# generator_cd4047.net
KiCad netlist of a schematic drawn in EAGLE
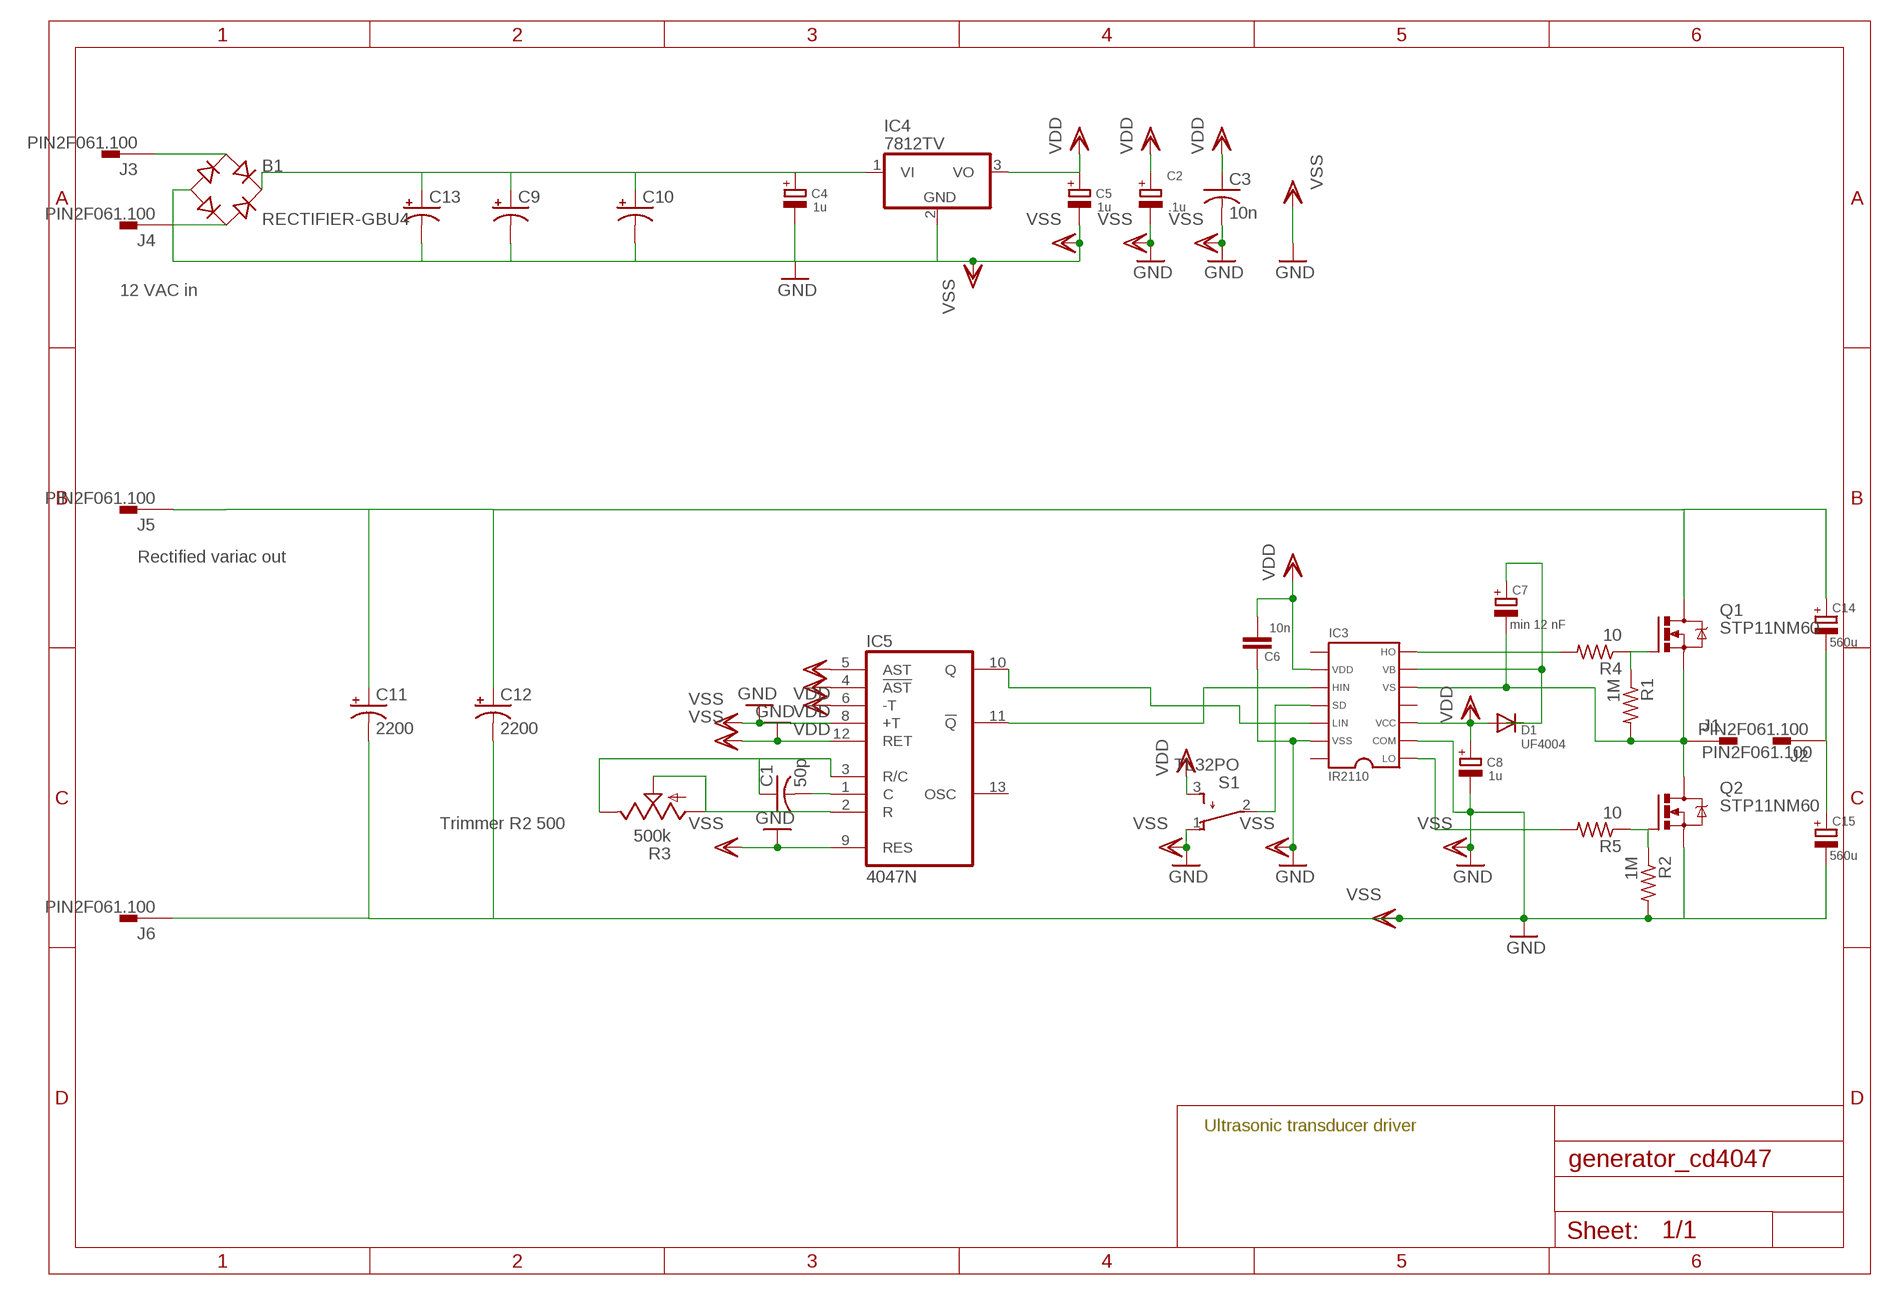
[diagram p0: schematic, sheet 1]

(export (version "E")
  (design (tool "Eeschema 10.0.6"))
  (components
    (comp (ref "B1")
      (value "RECTIFIER-GBU4")
      (footprint "eagle-import:GBU4")
      (libsource (lib "eagle-import") (part "RECTIFIER-GBU4"))
    )
    (comp (ref "C1")
      (value "50p")
      (footprint "eagle-import:C075-042X103")
      (libsource (lib "eagle-import") (part "C-US075-042X103"))
    )
    (comp (ref "C2")
      (value ".1u")
      (footprint "eagle-import:E5-8,5")
      (libsource (lib "eagle-import") (part "CPOL-EUE5-8.5"))
    )
    (comp (ref "C3")
      (value "10n")
      (footprint "eagle-import:C075-042X103")
      (libsource (lib "eagle-import") (part "C-US075-042X103"))
    )
    (comp (ref "C4")
      (value "1u")
      (footprint "eagle-import:E5-8,5")
      (libsource (lib "eagle-import") (part "CPOL-EUE5-8.5"))
    )
    (comp (ref "C5")
      (value "1u")
      (footprint "eagle-import:E5-8,5")
      (libsource (lib "eagle-import") (part "CPOL-EUE5-8.5"))
    )
    (comp (ref "C6")
      (value "10n")
      (footprint "eagle-import:C075-052X106")
      (libsource (lib "eagle-import") (part "C-EU075-052X106"))
    )
    (comp (ref "C7")
      (value "min 12 nF")
      (footprint "eagle-import:E5-8,5")
      (libsource (lib "eagle-import") (part "CPOL-EUE5-8.5"))
    )
    (comp (ref "C8")
      (value "1u")
      (footprint "eagle-import:E5-8,5")
      (libsource (lib "eagle-import") (part "CPOL-EUE5-8.5"))
    )
    (comp (ref "C9")
      (value "CPOL-USE7.5-18")
      (footprint "eagle-import:E7,5-18")
      (libsource (lib "eagle-import") (part "CPOL-USE7.5-18"))
    )
    (comp (ref "C10")
      (value "CPOL-USE7.5-18")
      (footprint "eagle-import:E7,5-18")
      (libsource (lib "eagle-import") (part "CPOL-USE7.5-18"))
    )
    (comp (ref "C11")
      (value "2200")
      (footprint "eagle-import:EB35D")
      (libsource (lib "eagle-import") (part "CPOL-USE10-35"))
    )
    (comp (ref "C12")
      (value "2200")
      (footprint "eagle-import:EB35D")
      (libsource (lib "eagle-import") (part "CPOL-USE10-35"))
    )
    (comp (ref "C13")
      (value "CPOL-USE7.5-18")
      (footprint "eagle-import:E7,5-18")
      (libsource (lib "eagle-import") (part "CPOL-USE7.5-18"))
    )
    (comp (ref "C14")
      (value "560u")
      (footprint "eagle-import:E7,5-16")
      (libsource (lib "eagle-import") (part "CPOL-EUE7.5-16"))
    )
    (comp (ref "C15")
      (value "560u")
      (footprint "eagle-import:E7,5-16")
      (libsource (lib "eagle-import") (part "CPOL-EUE7.5-16"))
    )
    (comp (ref "D1")
      (value "UF4004")
      (footprint "eagle-import:D-7.5")
      (libsource (lib "eagle-import") (part "DIODE-D-7.5"))
    )
    (comp (ref "IC3")
      (value "IR2110")
      (footprint "eagle-import:DIL14")
      (libsource (lib "eagle-import") (part "IR2110"))
    )
    (comp (ref "IC4")
      (value "7812TV")
      (footprint "eagle-import:TO220V")
      (libsource (lib "eagle-import") (part "78TV12"))
    )
    (comp (ref "IC5")
      (value "4047N")
      (footprint "eagle-import:DIL14")
      (libsource (lib "eagle-import") (part "4047N"))
    )
    (comp (ref "J1")
      (value "PIN2F061.100")
      (footprint "eagle-import:F061.100")
      (libsource (lib "eagle-import") (part "PIN2F061.100"))
    )
    (comp (ref "J2")
      (value "PIN2F061.100")
      (footprint "eagle-import:F061.100")
      (libsource (lib "eagle-import") (part "PIN2F061.100"))
    )
    (comp (ref "J3")
      (value "PIN2F061.100")
      (footprint "eagle-import:F061.100")
      (libsource (lib "eagle-import") (part "PIN2F061.100"))
    )
    (comp (ref "J4")
      (value "PIN2F061.100")
      (footprint "eagle-import:F061.100")
      (libsource (lib "eagle-import") (part "PIN2F061.100"))
    )
    (comp (ref "J5")
      (value "PIN2F061.100")
      (footprint "eagle-import:F061.100")
      (libsource (lib "eagle-import") (part "PIN2F061.100"))
    )
    (comp (ref "J6")
      (value "PIN2F061.100")
      (footprint "eagle-import:F061.100")
      (libsource (lib "eagle-import") (part "PIN2F061.100"))
    )
    (comp (ref "Q1")
      (value "STP11NM60")
      (footprint "eagle-import:TO220BV")
      (libsource (lib "eagle-import") (part "IRF530"))
    )
    (comp (ref "Q2")
      (value "STP11NM60")
      (footprint "eagle-import:TO220BV")
      (libsource (lib "eagle-import") (part "IRF530"))
    )
    (comp (ref "R1")
      (value "1M")
      (footprint "eagle-import:0207_10")
      (libsource (lib "eagle-import") (part "R-US_0207/10"))
    )
    (comp (ref "R2")
      (value "1M")
      (footprint "eagle-import:0207_10")
      (libsource (lib "eagle-import") (part "R-US_0207/10"))
    )
    (comp (ref "R3")
      (value "500k")
      (footprint "eagle-import:RJ9W")
      (libsource (lib "eagle-import") (part "TRIM_US-RJ9W"))
    )
    (comp (ref "R4")
      (value "10")
      (footprint "eagle-import:0207_10")
      (libsource (lib "eagle-import") (part "R-US_0207/10"))
    )
    (comp (ref "R5")
      (value "10")
      (footprint "eagle-import:0207_15")
      (libsource (lib "eagle-import") (part "R-US_0207/15"))
    )
    (comp (ref "S1")
      (value "TL32PO")
      (footprint "eagle-import:TL3XPO")
      (libsource (lib "eagle-import") (part "TL32PO"))
    )
  )
  (nets
    (net (code "1") (name "GND") (class "Default")
      (node (ref "B1") (pin "-") (pinfunction "-_-") (pintype "passive"))
      (node (ref "C10") (pin "-") (pinfunction "-_-") (pintype "passive"))
      (node (ref "C11") (pin "-") (pinfunction "-_-") (pintype "passive"))
      (node (ref "C12") (pin "-") (pinfunction "-_-") (pintype "passive"))
      (node (ref "C13") (pin "-") (pinfunction "-_-") (pintype "passive"))
      (node (ref "C15") (pin "-") (pinfunction "-_-") (pintype "passive"))
      (node (ref "C2") (pin "-") (pinfunction "-_-") (pintype "passive"))
      (node (ref "C3") (pin "2") (pinfunction "2_2") (pintype "passive"))
      (node (ref "C4") (pin "-") (pinfunction "-_-") (pintype "passive"))
      (node (ref "C5") (pin "-") (pinfunction "-_-") (pintype "passive"))
      (node (ref "C6") (pin "1") (pinfunction "1_1") (pintype "passive"))
      (node (ref "C8") (pin "-") (pinfunction "-_-") (pintype "passive"))
      (node (ref "C9") (pin "-") (pinfunction "-_-") (pintype "passive"))
      (node (ref "IC3") (pin "13") (pinfunction "13_13") (pintype "passive"))
      (node (ref "IC3") (pin "2") (pinfunction "2_2") (pintype "passive"))
      (node (ref "IC4") (pin "2") (pinfunction "GND_2") (pintype "passive"))
      (node (ref "IC5") (pin "12") (pinfunction "RET_12") (pintype "input"))
      (node (ref "IC5") (pin "8") (pinfunction "+T_8") (pintype "input"))
      (node (ref "IC5") (pin "9") (pinfunction "RES_9") (pintype "input"))
      (node (ref "J6") (pin "A1") (pinfunction "1_A1") (pintype "passive"))
      (node (ref "J6") (pin "A2") (pinfunction "1_A2") (pintype "passive"))
      (node (ref "Q2") (pin "S") (pinfunction "S_S") (pintype "passive"))
      (node (ref "R2") (pin "2") (pinfunction "2_2") (pintype "passive"))
      (node (ref "S1") (pin "1") (pinfunction "O_1") (pintype "passive"))
    )
    (net (code "2") (name "Net-(B1-PadAC1)") (class "Default")
      (node (ref "B1") (pin "AC1") (pinfunction "AC1_AC1") (pintype "passive"))
      (node (ref "J3") (pin "A1") (pinfunction "1_A1") (pintype "passive"))
      (node (ref "J3") (pin "A2") (pinfunction "1_A2") (pintype "passive"))
    )
    (net (code "3") (name "Net-(B1-PadAC2)") (class "Default")
      (node (ref "B1") (pin "AC2") (pinfunction "AC2_AC2") (pintype "passive"))
      (node (ref "J4") (pin "A1") (pinfunction "1_A1") (pintype "passive"))
      (node (ref "J4") (pin "A2") (pinfunction "1_A2") (pintype "passive"))
    )
    (net (code "4") (name "Net-(C7-Pad+)") (class "Default")
      (node (ref "C7") (pin "+") (pinfunction "+_+") (pintype "passive"))
      (node (ref "D1") (pin "C") (pinfunction "C_C") (pintype "passive"))
      (node (ref "IC3") (pin "6") (pinfunction "6_6") (pintype "passive"))
    )
    (net (code "5") (name "Net-(C7-Pad-)") (class "Default")
      (node (ref "C7") (pin "-") (pinfunction "-_-") (pintype "passive"))
      (node (ref "IC3") (pin "5") (pinfunction "5_5") (pintype "passive"))
      (node (ref "J1") (pin "A1") (pinfunction "1_A1") (pintype "passive"))
      (node (ref "J1") (pin "A2") (pinfunction "1_A2") (pintype "passive"))
      (node (ref "Q1") (pin "S") (pinfunction "S_S") (pintype "passive"))
      (node (ref "Q2") (pin "D") (pinfunction "D_D") (pintype "passive"))
      (node (ref "R1") (pin "2") (pinfunction "2_2") (pintype "passive"))
    )
    (net (code "6") (name "Net-(C11-Pad+)") (class "Default")
      (node (ref "C11") (pin "+") (pinfunction "+_+") (pintype "passive"))
      (node (ref "C12") (pin "+") (pinfunction "+_+") (pintype "passive"))
      (node (ref "C14") (pin "+") (pinfunction "+_+") (pintype "passive"))
      (node (ref "J5") (pin "A1") (pinfunction "1_A1") (pintype "passive"))
      (node (ref "J5") (pin "A2") (pinfunction "1_A2") (pintype "passive"))
      (node (ref "Q1") (pin "D") (pinfunction "D_D") (pintype "passive"))
    )
    (net (code "7") (name "Net-(C14-Pad-)") (class "Default")
      (node (ref "C14") (pin "-") (pinfunction "-_-") (pintype "passive"))
      (node (ref "C15") (pin "+") (pinfunction "+_+") (pintype "passive"))
      (node (ref "J2") (pin "A1") (pinfunction "1_A1") (pintype "passive"))
      (node (ref "J2") (pin "A2") (pinfunction "1_A2") (pintype "passive"))
    )
    (net (code "8") (name "Net-(IC3-Pad1)") (class "Default")
      (node (ref "IC3") (pin "1") (pinfunction "1_1") (pintype "passive"))
      (node (ref "R5") (pin "2") (pinfunction "2_2") (pintype "passive"))
    )
    (net (code "9") (name "Net-(IC3-Pad7)") (class "Default")
      (node (ref "IC3") (pin "7") (pinfunction "7_7") (pintype "passive"))
      (node (ref "R4") (pin "2") (pinfunction "2_2") (pintype "passive"))
    )
    (net (code "10") (name "Net-(IC4-VI)") (class "Default")
      (node (ref "B1") (pin "+") (pinfunction "+_+") (pintype "passive"))
      (node (ref "C10") (pin "+") (pinfunction "+_+") (pintype "passive"))
      (node (ref "C13") (pin "+") (pinfunction "+_+") (pintype "passive"))
      (node (ref "C4") (pin "+") (pinfunction "+_+") (pintype "passive"))
      (node (ref "C9") (pin "+") (pinfunction "+_+") (pintype "passive"))
      (node (ref "IC4") (pin "1") (pinfunction "VI_1") (pintype "input"))
    )
    (net (code "11") (name "Net-(IC5A-C)") (class "Default")
      (node (ref "C1") (pin "2") (pinfunction "2_2") (pintype "passive"))
      (node (ref "IC5") (pin "1") (pinfunction "C_1") (pintype "input"))
    )
    (net (code "12") (name "Net-(IC5A-Q)") (class "Default")
      (node (ref "IC3") (pin "12") (pinfunction "12_12") (pintype "passive"))
      (node (ref "IC5") (pin "10") (pinfunction "Q_10") (pintype "output"))
    )
    (net (code "13") (name "Net-(IC5A-R)") (class "Default")
      (node (ref "IC5") (pin "2") (pinfunction "R_2") (pintype "input"))
      (node (ref "R3") (pin "A") (pinfunction "A_A") (pintype "passive"))
      (node (ref "R3") (pin "S") (pinfunction "S_S") (pintype "passive"))
    )
    (net (code "14") (name "Net-(IC5A-R{slash}C)") (class "Default")
      (node (ref "C1") (pin "1") (pinfunction "1_1") (pintype "passive"))
      (node (ref "IC5") (pin "3") (pinfunction "R/C_3") (pintype "input"))
      (node (ref "R3") (pin "E") (pinfunction "E_E") (pintype "passive"))
    )
    (net (code "15") (name "Net-(IC5A-~{Q})") (class "Default")
      (node (ref "IC3") (pin "10") (pinfunction "10_10") (pintype "passive"))
      (node (ref "IC5") (pin "11") (pinfunction "~{Q}_11") (pintype "output"))
    )
    (net (code "16") (name "Net-(Q1-PadG)") (class "Default")
      (node (ref "Q1") (pin "G") (pinfunction "G_G") (pintype "passive"))
      (node (ref "R1") (pin "1") (pinfunction "1_1") (pintype "passive"))
      (node (ref "R4") (pin "1") (pinfunction "1_1") (pintype "passive"))
    )
    (net (code "17") (name "Net-(Q2-PadG)") (class "Default")
      (node (ref "Q2") (pin "G") (pinfunction "G_G") (pintype "passive"))
      (node (ref "R2") (pin "1") (pinfunction "1_1") (pintype "passive"))
      (node (ref "R5") (pin "1") (pinfunction "1_1") (pintype "passive"))
    )
    (net (code "18") (name "Net-(S1-P)") (class "Default")
      (node (ref "IC3") (pin "11") (pinfunction "11_11") (pintype "passive"))
      (node (ref "S1") (pin "2") (pinfunction "P_2") (pintype "passive"))
    )
    (net (code "19") (name "VDD") (class "Default")
      (node (ref "C2") (pin "+") (pinfunction "+_+") (pintype "passive"))
      (node (ref "C3") (pin "1") (pinfunction "1_1") (pintype "passive"))
      (node (ref "C5") (pin "+") (pinfunction "+_+") (pintype "passive"))
      (node (ref "C6") (pin "2") (pinfunction "2_2") (pintype "passive"))
      (node (ref "C8") (pin "+") (pinfunction "+_+") (pintype "passive"))
      (node (ref "D1") (pin "A") (pinfunction "A_A") (pintype "passive"))
      (node (ref "IC3") (pin "3") (pinfunction "3_3") (pintype "passive"))
      (node (ref "IC3") (pin "9") (pinfunction "9_9") (pintype "passive"))
      (node (ref "IC4") (pin "3") (pinfunction "VO_3") (pintype "passive"))
      (node (ref "IC5") (pin "4") (pinfunction "~{AST}_4") (pintype "input"))
      (node (ref "IC5") (pin "5") (pinfunction "AST_5") (pintype "input"))
      (node (ref "IC5") (pin "6") (pinfunction "-T_6") (pintype "input"))
      (node (ref "S1") (pin "3") (pinfunction "S_3") (pintype "passive"))
    )
    (net (code "20") (name "unconnected-(IC3-Pad4)") (class "Default")
      (node (ref "IC3") (pin "4") (pinfunction "4_4") (pintype "passive"))
    )
    (net (code "21") (name "unconnected-(IC3-Pad8)") (class "Default")
      (node (ref "IC3") (pin "8") (pinfunction "8_8") (pintype "passive"))
    )
    (net (code "22") (name "unconnected-(IC3-Pad14)") (class "Default")
      (node (ref "IC3") (pin "14") (pinfunction "14_14") (pintype "passive"))
    )
    (net (code "23") (name "unconnected-(IC5A-OSC-Pad13)") (class "Default")
      (node (ref "IC5") (pin "13") (pinfunction "OSC_13") (pintype "output"))
    )
  )
)
